# BLEmicro_IMU_ArduinoV3.net
KiCad netlist of a schematic drawn in EAGLE
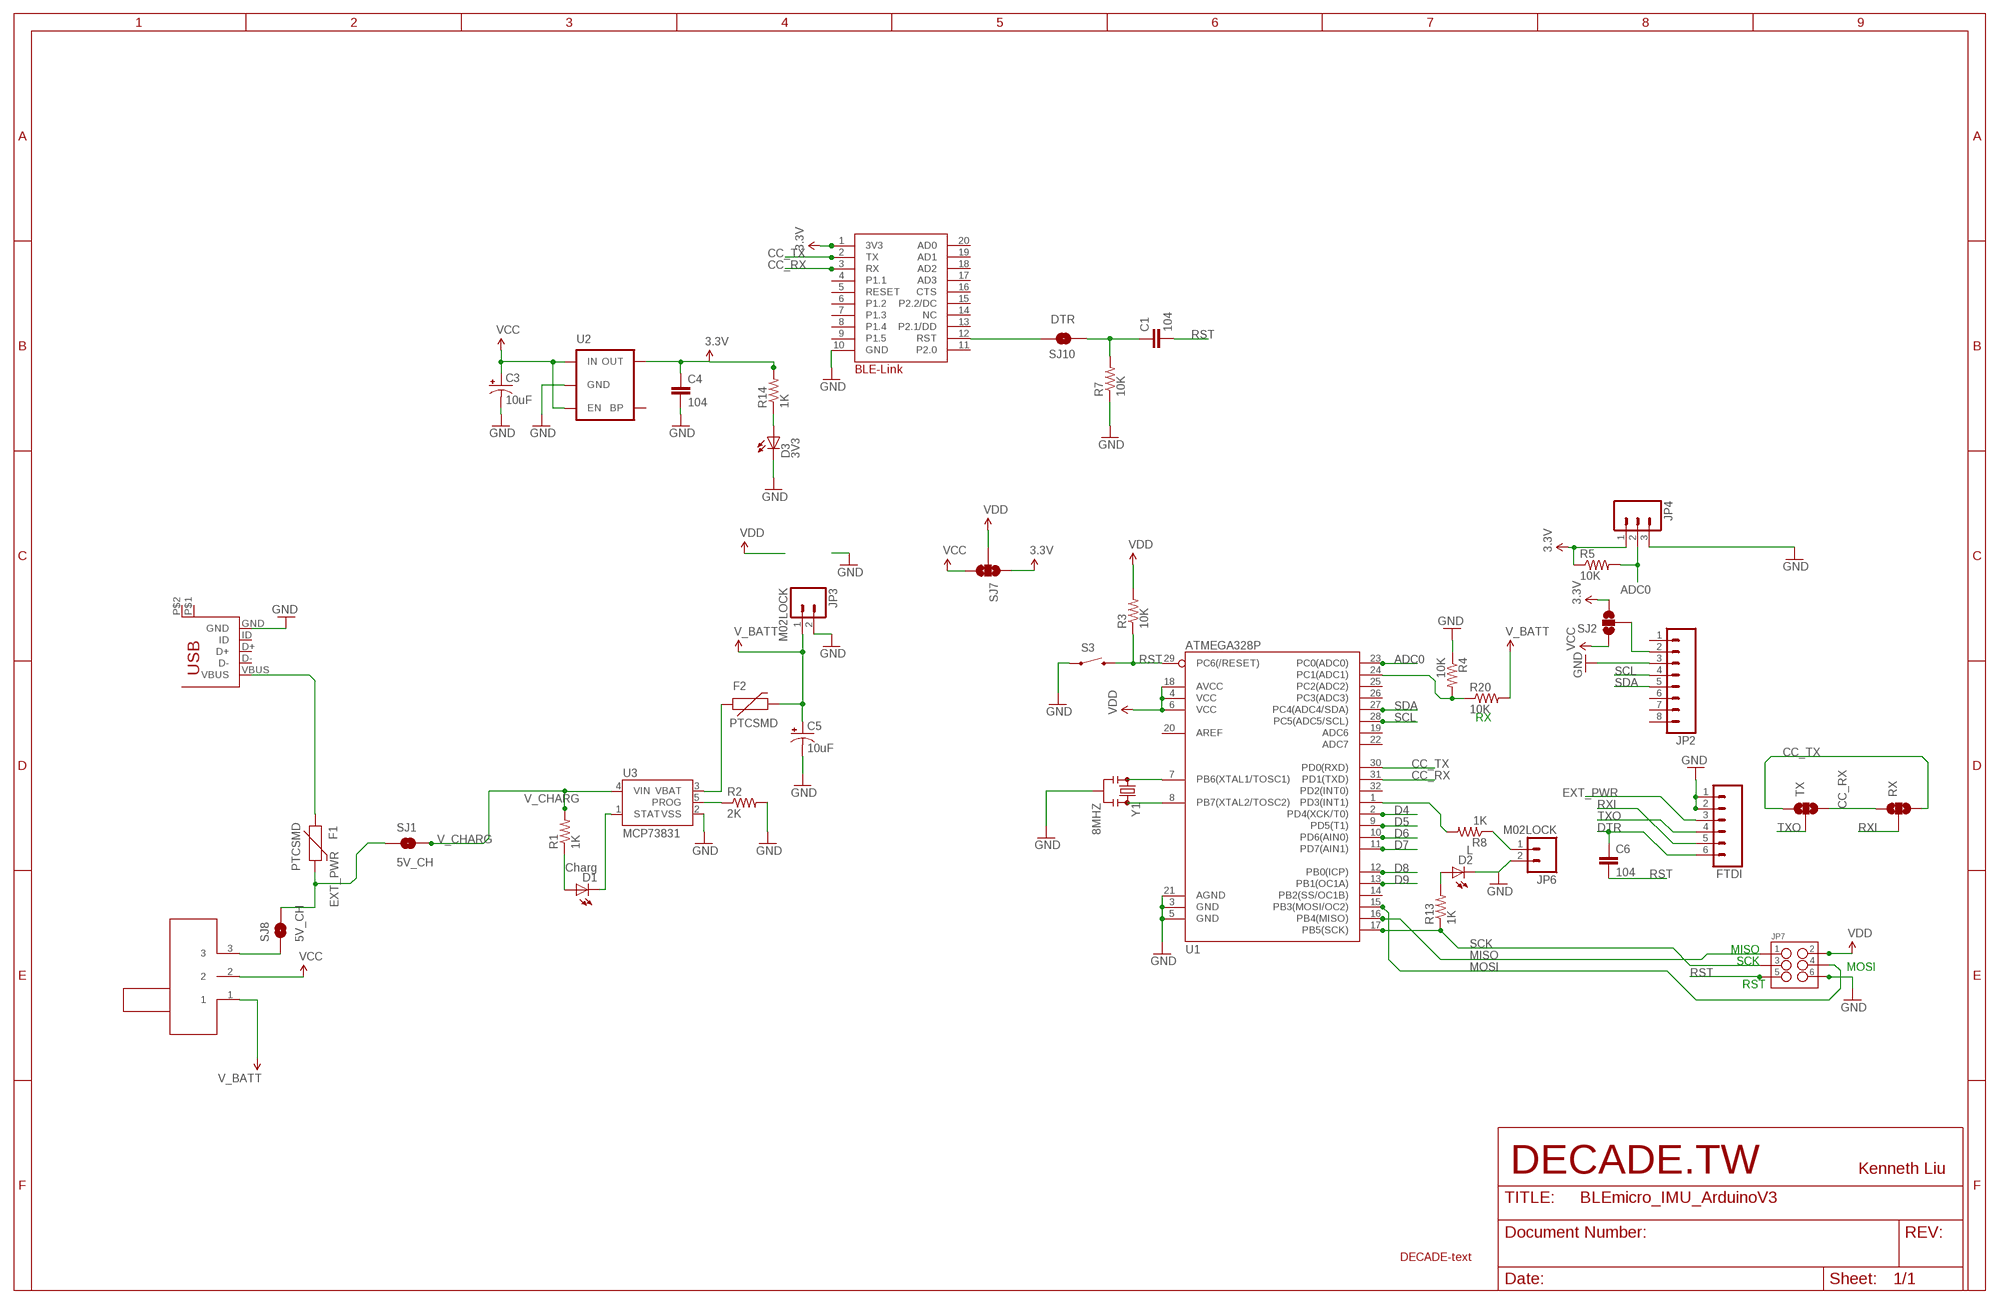
[diagram p0: schematic, sheet 1]

(export (version "E")
  (design (tool "Eeschema 10.0.6"))
  (components
    (comp (ref "C1")
      (value "104")
      (footprint "eagle-import:0603-CAP")
      (libsource (lib "eagle-import") (part "CAP0603-CAP"))
    )
    (comp (ref "C3")
      (value "10uF")
      (footprint "eagle-import:EIA3216")
      (libsource (lib "eagle-import") (part "CAP_POL1206"))
    )
    (comp (ref "C4")
      (value "104")
      (footprint "eagle-import:0603-CAP")
      (libsource (lib "eagle-import") (part "CAP0603-CAP"))
    )
    (comp (ref "C5")
      (value "10uF")
      (footprint "eagle-import:EIA3216")
      (libsource (lib "eagle-import") (part "CAP_POL1206"))
    )
    (comp (ref "C6")
      (value "104")
      (footprint "eagle-import:0603-CAP")
      (libsource (lib "eagle-import") (part "CAP0603-CAP"))
    )
    (comp (ref "D1")
      (value "Charg")
      (footprint "eagle-import:LED-0603")
      (libsource (lib "eagle-import") (part "LED-RED0603"))
    )
    (comp (ref "D2")
      (value "L")
      (footprint "eagle-import:LED-0603")
      (libsource (lib "eagle-import") (part "LED-RED0603"))
    )
    (comp (ref "D3")
      (value "3V3")
      (footprint "eagle-import:LED-0603")
      (libsource (lib "eagle-import") (part "LED-RED0603"))
    )
    (comp (ref "F1")
      (value "PTCSMD")
      (footprint "eagle-import:PTC-1206")
      (libsource (lib "eagle-import") (part "PTCSMD"))
    )
    (comp (ref "F2")
      (value "PTCSMD")
      (footprint "eagle-import:PTC-1206")
      (libsource (lib "eagle-import") (part "PTCSMD"))
    )
    (comp (ref "FTDI")
      (value "M06NO_SILK")
      (footprint "eagle-import:1X06_NO_SILK")
      (libsource (lib "eagle-import") (part "M06NO_SILK"))
    )
    (comp (ref "JP2")
      (value "M08NO_SILK")
      (footprint "eagle-import:1X08_NO_SILK")
      (libsource (lib "eagle-import") (part "M08NO_SILK"))
    )
    (comp (ref "JP3")
      (value "M02LOCK")
      (footprint "eagle-import:1X02_LOCK")
      (libsource (lib "eagle-import") (part "M02LOCK"))
    )
    (comp (ref "JP4")
      (value "M03PTH")
      (footprint "eagle-import:1X03")
      (libsource (lib "eagle-import") (part "M03PTH"))
    )
    (comp (ref "JP6")
      (value "M02LOCK")
      (footprint "eagle-import:1X02_LOCK")
      (libsource (lib "eagle-import") (part "M02LOCK"))
    )
    (comp (ref "JP7")
      (value "M03X2NO_SILK")
      (footprint "eagle-import:2X3-NS")
      (libsource (lib "eagle-import") (part "M03X2NO_SILK"))
    )
    (comp (ref "R1")
      (value "1K")
      (footprint "eagle-import:0603-RES")
      (libsource (lib "eagle-import") (part "RESISTOR0603-RES"))
    )
    (comp (ref "R2")
      (value "2K")
      (footprint "eagle-import:0603-RES")
      (libsource (lib "eagle-import") (part "RESISTOR0603-RES"))
    )
    (comp (ref "R3")
      (value "10K")
      (footprint "eagle-import:0603-RES")
      (libsource (lib "eagle-import") (part "RESISTOR0603-RES"))
    )
    (comp (ref "R4")
      (value "10K")
      (footprint "eagle-import:0603-RES")
      (libsource (lib "eagle-import") (part "RESISTOR0603-RES"))
    )
    (comp (ref "R5")
      (value "10K")
      (footprint "eagle-import:0603-RES")
      (libsource (lib "eagle-import") (part "RESISTOR0603-RES"))
    )
    (comp (ref "R7")
      (value "10K")
      (footprint "eagle-import:0603-RES")
      (libsource (lib "eagle-import") (part "RESISTOR0603-RES"))
    )
    (comp (ref "R8")
      (value "1K")
      (footprint "eagle-import:0603-RES")
      (libsource (lib "eagle-import") (part "RESISTOR0603-RES"))
    )
    (comp (ref "R13")
      (value "1K")
      (footprint "eagle-import:0603-RES")
      (libsource (lib "eagle-import") (part "RESISTOR0603-RES"))
    )
    (comp (ref "R14")
      (value "1K")
      (footprint "eagle-import:0603-RES")
      (libsource (lib "eagle-import") (part "RESISTOR0603-RES"))
    )
    (comp (ref "R20")
      (value "10K")
      (footprint "eagle-import:0603-RES")
      (libsource (lib "eagle-import") (part "RESISTOR0603-RES"))
    )
    (comp (ref "RX")
      (value "SOLDERJUMPER_2WAYS")
      (footprint "eagle-import:SJ_3")
      (libsource (lib "eagle-import") (part "SOLDERJUMPER_2WAYS"))
    )
    (comp (ref "S3")
      (value "SWITCH-MOMENTARY-2SMD-1101NE")
      (footprint "eagle-import:TACTILE-SWITCH-1101NE")
      (libsource (lib "eagle-import") (part "SWITCH-MOMENTARY-2SMD-1101NE"))
    )
    (comp (ref "SJ1")
      (value "5V_CH")
      (footprint "eagle-import:SJ_2S")
      (libsource (lib "eagle-import") (part "SOLDERJUMPER-OLDNC"))
    )
    (comp (ref "SJ2")
      (value "SOLDERJUMPER_2WAYS")
      (footprint "eagle-import:SJ_3")
      (libsource (lib "eagle-import") (part "SOLDERJUMPER_2WAYS"))
    )
    (comp (ref "SJ7")
      (value "SOLDERJUMPER_2WAYS")
      (footprint "eagle-import:SJ_3")
      (libsource (lib "eagle-import") (part "SOLDERJUMPER_2WAYS"))
    )
    (comp (ref "SJ8")
      (value "5V_CH")
      (footprint "eagle-import:SJ_2S")
      (libsource (lib "eagle-import") (part "SOLDERJUMPER-OLDNC"))
    )
    (comp (ref "SJ10")
      (value "DTR")
      (footprint "eagle-import:SJ_2S")
      (libsource (lib "eagle-import") (part "SOLDERJUMPER-OLDNC"))
    )
    (comp (ref "TX")
      (value "SOLDERJUMPER_2WAYS")
      (footprint "eagle-import:SJ_3")
      (libsource (lib "eagle-import") (part "SOLDERJUMPER_2WAYS"))
    )
    (comp (ref "U$1")
      (value "BLE-LINK")
      (footprint "eagle-import:XBEE-1_LOCK")
      (libsource (lib "eagle-import") (part "BLE-LINK"))
    )
    (comp (ref "U$2")
      (value "USB_MICRO_7PIN")
      (footprint "eagle-import:USB-MICROB-7PIN")
      (libsource (lib "eagle-import") (part "USB_MICRO_7PIN"))
    )
    (comp (ref "U$4")
      (value "DECADE-SW-SMALL")
      (footprint "eagle-import:DECADE-SW-SM")
      (libsource (lib "eagle-import") (part "DECADE-SW-SMALL"))
    )
    (comp (ref "U$7")
      (value "DECADE-LOGO-TEXT")
      (footprint "eagle-import:DECADE-LOGO-TEXT")
      (libsource (lib "eagle-import") (part "DECADE-LOGO-TEXT"))
    )
    (comp (ref "U1")
      (value "ATMEGA328P")
      (footprint "eagle-import:TQFP32-08")
      (libsource (lib "eagle-import") (part "ATMEGA328_SMT"))
    )
    (comp (ref "U2")
      (value "MIC52053.3V")
      (footprint "eagle-import:SOT23-5")
      (libsource (lib "eagle-import") (part "MIC52053.3V"))
    )
    (comp (ref "U3")
      (value "MCP73831")
      (footprint "eagle-import:SOT23-5")
      (libsource (lib "eagle-import") (part "MCP73831"))
    )
    (comp (ref "Y1")
      (value "8MHZ")
      (footprint "eagle-import:RESONATOR-SMD")
      (libsource (lib "eagle-import") (part "RESONATOR8MHZ"))
    )
  )
  (nets
    (net (code "1") (name "/ADC0") (class "Default")
      (node (ref "JP4") (pin "2") (pinfunction "2_2") (pintype "passive"))
      (node (ref "R5") (pin "2") (pinfunction "2_2") (pintype "passive"))
      (node (ref "U1") (pin "23") (pinfunction "PC0(ADC0)_23") (pintype "bidirectional"))
    )
    (net (code "2") (name "/CC_RX") (class "Default")
      (node (ref "RX") (pin "1") (pinfunction "1_1") (pintype "passive"))
      (node (ref "TX") (pin "3") (pinfunction "3_3") (pintype "passive"))
      (node (ref "U$1") (pin "3") (pinfunction "RX_3") (pintype "bidirectional"))
      (node (ref "U1") (pin "31") (pinfunction "PD1(TXD)_31") (pintype "bidirectional"))
    )
    (net (code "3") (name "/CC_TX") (class "Default")
      (node (ref "RX") (pin "3") (pinfunction "3_3") (pintype "passive"))
      (node (ref "TX") (pin "1") (pinfunction "1_1") (pintype "passive"))
      (node (ref "U$1") (pin "2") (pinfunction "TX_2") (pintype "bidirectional"))
      (node (ref "U1") (pin "30") (pinfunction "PD0(RXD)_30") (pintype "bidirectional"))
    )
    (net (code "4") (name "/D4") (class "Default")
      (node (ref "U1") (pin "2") (pinfunction "PD4(XCK/T0)_2") (pintype "bidirectional"))
    )
    (net (code "5") (name "/D5") (class "Default")
      (node (ref "U1") (pin "9") (pinfunction "PD5(T1)_9") (pintype "bidirectional"))
    )
    (net (code "6") (name "/D6") (class "Default")
      (node (ref "U1") (pin "10") (pinfunction "PD6(AIN0)_10") (pintype "bidirectional"))
    )
    (net (code "7") (name "/D7") (class "Default")
      (node (ref "U1") (pin "11") (pinfunction "PD7(AIN1)_11") (pintype "bidirectional"))
    )
    (net (code "8") (name "/D8") (class "Default")
      (node (ref "U1") (pin "12") (pinfunction "PB0(ICP)_12") (pintype "bidirectional"))
    )
    (net (code "9") (name "/D9") (class "Default")
      (node (ref "U1") (pin "13") (pinfunction "PB1(OC1A)_13") (pintype "bidirectional"))
    )
    (net (code "10") (name "/DTR") (class "Default")
      (node (ref "C6") (pin "1") (pinfunction "1_1") (pintype "passive"))
      (node (ref "FTDI") (pin "6") (pinfunction "6_6") (pintype "passive"))
    )
    (net (code "11") (name "/EXT_PWR") (class "Default")
      (node (ref "F1") (pin "2") (pinfunction "2_2") (pintype "bidirectional"))
      (node (ref "FTDI") (pin "3") (pinfunction "3_3") (pintype "passive"))
      (node (ref "SJ1") (pin "1") (pinfunction "1_1") (pintype "passive"))
      (node (ref "SJ8") (pin "2") (pinfunction "2_2") (pintype "passive"))
    )
    (net (code "12") (name "/MISO") (class "Default")
      (node (ref "JP7") (pin "1") (pinfunction "1_1") (pintype "bidirectional"))
      (node (ref "U1") (pin "16") (pinfunction "PB4(MISO)_16") (pintype "bidirectional"))
    )
    (net (code "13") (name "/MOSI") (class "Default")
      (node (ref "JP7") (pin "4") (pinfunction "4_4") (pintype "bidirectional"))
      (node (ref "U1") (pin "15") (pinfunction "PB3(MOSI/OC2)_15") (pintype "bidirectional"))
    )
    (net (code "14") (name "/RST") (class "Default")
      (node (ref "C1") (pin "2") (pinfunction "2_2") (pintype "passive"))
      (node (ref "C6") (pin "2") (pinfunction "2_2") (pintype "passive"))
      (node (ref "JP7") (pin "5") (pinfunction "5_5") (pintype "bidirectional"))
      (node (ref "R3") (pin "1") (pinfunction "1_1") (pintype "passive"))
      (node (ref "S3") (pin "2") (pinfunction "2_2") (pintype "passive"))
      (node (ref "U1") (pin "29") (pinfunction "PC6(/RESET)_29") (pintype "bidirectional"))
    )
    (net (code "15") (name "/RXI") (class "Default")
      (node (ref "FTDI") (pin "5") (pinfunction "5_5") (pintype "passive"))
      (node (ref "RX") (pin "2") (pinfunction "2_2") (pintype "passive"))
    )
    (net (code "16") (name "/SCK") (class "Default")
      (node (ref "JP7") (pin "3") (pinfunction "3_3") (pintype "bidirectional"))
      (node (ref "R13") (pin "1") (pinfunction "1_1") (pintype "passive"))
      (node (ref "U1") (pin "17") (pinfunction "PB5(SCK)_17") (pintype "bidirectional"))
    )
    (net (code "17") (name "/SCL") (class "Default")
      (node (ref "JP2") (pin "4") (pinfunction "4_4") (pintype "passive"))
      (node (ref "U1") (pin "28") (pinfunction "PC5(ADC5/SCL)_28") (pintype "bidirectional"))
    )
    (net (code "18") (name "/SDA") (class "Default")
      (node (ref "JP2") (pin "5") (pinfunction "5_5") (pintype "passive"))
      (node (ref "U1") (pin "27") (pinfunction "PC4(ADC4/SDA)_27") (pintype "bidirectional"))
    )
    (net (code "19") (name "/TXO") (class "Default")
      (node (ref "FTDI") (pin "4") (pinfunction "4_4") (pintype "passive"))
      (node (ref "TX") (pin "2") (pinfunction "2_2") (pintype "passive"))
    )
    (net (code "20") (name "/V_CHARG") (class "Default")
      (node (ref "R1") (pin "2") (pinfunction "2_2") (pintype "passive"))
      (node (ref "SJ1") (pin "2") (pinfunction "2_2") (pintype "passive"))
      (node (ref "U3") (pin "4") (pinfunction "VIN_4") (pintype "power_in"))
    )
    (net (code "21") (name "3.3V") (class "Default")
      (node (ref "C4") (pin "1") (pinfunction "1_1") (pintype "passive"))
      (node (ref "JP4") (pin "1") (pinfunction "1_1") (pintype "passive"))
      (node (ref "R14") (pin "2") (pinfunction "2_2") (pintype "passive"))
      (node (ref "R5") (pin "1") (pinfunction "1_1") (pintype "passive"))
      (node (ref "SJ2") (pin "3") (pinfunction "3_3") (pintype "passive"))
      (node (ref "SJ7") (pin "1") (pinfunction "1_1") (pintype "passive"))
      (node (ref "U$1") (pin "1") (pinfunction "3V3_1") (pintype "bidirectional"))
      (node (ref "U2") (pin "5") (pinfunction "OUT_5") (pintype "passive"))
    )
    (net (code "22") (name "GND") (class "Default")
      (node (ref "C3") (pin "C") (pinfunction "-_C") (pintype "passive"))
      (node (ref "C4") (pin "2") (pinfunction "2_2") (pintype "passive"))
      (node (ref "C5") (pin "C") (pinfunction "-_C") (pintype "passive"))
      (node (ref "D2") (pin "C") (pinfunction "C_C") (pintype "passive"))
      (node (ref "D3") (pin "C") (pinfunction "C_C") (pintype "passive"))
      (node (ref "FTDI") (pin "1") (pinfunction "1_1") (pintype "passive"))
      (node (ref "FTDI") (pin "2") (pinfunction "2_2") (pintype "passive"))
      (node (ref "JP2") (pin "3") (pinfunction "3_3") (pintype "passive"))
      (node (ref "JP3") (pin "2") (pinfunction "2_2") (pintype "passive"))
      (node (ref "JP4") (pin "3") (pinfunction "3_3") (pintype "passive"))
      (node (ref "JP6") (pin "2") (pinfunction "2_2") (pintype "passive"))
      (node (ref "JP7") (pin "6") (pinfunction "6_6") (pintype "bidirectional"))
      (node (ref "R2") (pin "2") (pinfunction "2_2") (pintype "passive"))
      (node (ref "R4") (pin "1") (pinfunction "1_1") (pintype "passive"))
      (node (ref "R7") (pin "1") (pinfunction "1_1") (pintype "passive"))
      (node (ref "S3") (pin "1") (pinfunction "1_1") (pintype "passive"))
      (node (ref "U$1") (pin "10") (pinfunction "GND_10") (pintype "bidirectional"))
      (node (ref "U$2") (pin "GND") (pinfunction "GND_GND") (pintype "bidirectional"))
      (node (ref "U1") (pin "21") (pinfunction "AGND_21") (pintype "bidirectional"))
      (node (ref "U1") (pin "3") (pinfunction "GND_3") (pintype "bidirectional"))
      (node (ref "U1") (pin "5") (pinfunction "GND_5") (pintype "bidirectional"))
      (node (ref "U2") (pin "2") (pinfunction "GND_2") (pintype "input"))
      (node (ref "U3") (pin "2") (pinfunction "VSS_2") (pintype "power_in"))
      (node (ref "Y1") (pin "2") (pinfunction "2_2") (pintype "passive"))
    )
    (net (code "23") (name "Net-(C1-Pad1)") (class "Default")
      (node (ref "C1") (pin "1") (pinfunction "1_1") (pintype "passive"))
      (node (ref "R7") (pin "2") (pinfunction "2_2") (pintype "passive"))
      (node (ref "SJ10") (pin "1") (pinfunction "1_1") (pintype "passive"))
    )
    (net (code "24") (name "Net-(D1-PadA)") (class "Default")
      (node (ref "D1") (pin "A") (pinfunction "A_A") (pintype "passive"))
      (node (ref "R1") (pin "1") (pinfunction "1_1") (pintype "passive"))
    )
    (net (code "25") (name "Net-(D2-PadA)") (class "Default")
      (node (ref "D2") (pin "A") (pinfunction "A_A") (pintype "passive"))
      (node (ref "R13") (pin "2") (pinfunction "2_2") (pintype "passive"))
    )
    (net (code "26") (name "Net-(D3-PadA)") (class "Default")
      (node (ref "D3") (pin "A") (pinfunction "A_A") (pintype "passive"))
      (node (ref "R14") (pin "1") (pinfunction "1_1") (pintype "passive"))
    )
    (net (code "27") (name "Net-(F1-Pad1)") (class "Default")
      (node (ref "F1") (pin "1") (pinfunction "1_1") (pintype "bidirectional"))
      (node (ref "U$2") (pin "VBUS") (pinfunction "VBUS_VBUS") (pintype "bidirectional"))
    )
    (net (code "28") (name "Net-(JP2-Pad2)") (class "Default")
      (node (ref "JP2") (pin "2") (pinfunction "2_2") (pintype "passive"))
      (node (ref "SJ2") (pin "2") (pinfunction "2_2") (pintype "passive"))
    )
    (net (code "29") (name "Net-(JP6-Pad1)") (class "Default")
      (node (ref "JP6") (pin "1") (pinfunction "1_1") (pintype "passive"))
      (node (ref "R8") (pin "1") (pinfunction "1_1") (pintype "passive"))
    )
    (net (code "30") (name "Net-(SJ8-Pad1)") (class "Default")
      (node (ref "SJ8") (pin "1") (pinfunction "1_1") (pintype "passive"))
      (node (ref "U$4") (pin "3") (pinfunction "3_3") (pintype "bidirectional"))
    )
    (net (code "31") (name "Net-(U$1-RST)") (class "Default")
      (node (ref "SJ10") (pin "2") (pinfunction "2_2") (pintype "passive"))
      (node (ref "U$1") (pin "12") (pinfunction "RST_12") (pintype "bidirectional"))
    )
    (net (code "32") (name "Net-(U1-PB6(XTAL1{slash}TOSC1))") (class "Default")
      (node (ref "U1") (pin "7") (pinfunction "PB6(XTAL1/TOSC1)_7") (pintype "bidirectional"))
      (node (ref "Y1") (pin "1") (pinfunction "1_1") (pintype "passive"))
    )
    (net (code "33") (name "Net-(U1-PB7(XTAL2{slash}TOSC2))") (class "Default")
      (node (ref "U1") (pin "8") (pinfunction "PB7(XTAL2/TOSC2)_8") (pintype "bidirectional"))
      (node (ref "Y1") (pin "3") (pinfunction "3_3") (pintype "passive"))
    )
    (net (code "34") (name "Net-(U1-PC1(ADC1))") (class "Default")
      (node (ref "R20") (pin "1") (pinfunction "1_1") (pintype "passive"))
      (node (ref "R4") (pin "2") (pinfunction "2_2") (pintype "passive"))
      (node (ref "U1") (pin "24") (pinfunction "PC1(ADC1)_24") (pintype "bidirectional"))
    )
    (net (code "35") (name "Net-(U1-PD3(INT1))") (class "Default")
      (node (ref "R8") (pin "2") (pinfunction "2_2") (pintype "passive"))
      (node (ref "U1") (pin "1") (pinfunction "PD3(INT1)_1") (pintype "bidirectional"))
    )
    (net (code "36") (name "Net-(U3-PROG)") (class "Default")
      (node (ref "R2") (pin "1") (pinfunction "1_1") (pintype "passive"))
      (node (ref "U3") (pin "5") (pinfunction "PROG_5") (pintype "input"))
    )
    (net (code "37") (name "Net-(U3-STAT)") (class "Default")
      (node (ref "D1") (pin "C") (pinfunction "C_C") (pintype "passive"))
      (node (ref "U3") (pin "1") (pinfunction "STAT_1") (pintype "output"))
    )
    (net (code "38") (name "Net-(U3-VBAT)") (class "Default")
      (node (ref "F2") (pin "1") (pinfunction "1_1") (pintype "bidirectional"))
      (node (ref "U3") (pin "3") (pinfunction "VBAT_3") (pintype "power_in"))
    )
    (net (code "39") (name "VCC") (class "Default")
      (node (ref "C3") (pin "A") (pinfunction "+_A") (pintype "passive"))
      (node (ref "SJ2") (pin "1") (pinfunction "1_1") (pintype "passive"))
      (node (ref "SJ7") (pin "3") (pinfunction "3_3") (pintype "passive"))
      (node (ref "U$4") (pin "2") (pinfunction "2_2") (pintype "bidirectional"))
      (node (ref "U2") (pin "1") (pinfunction "IN_1") (pintype "input"))
      (node (ref "U2") (pin "3") (pinfunction "EN_3") (pintype "input"))
    )
    (net (code "40") (name "VDD") (class "Default")
      (node (ref "JP7") (pin "2") (pinfunction "2_2") (pintype "bidirectional"))
      (node (ref "R3") (pin "2") (pinfunction "2_2") (pintype "passive"))
      (node (ref "SJ7") (pin "2") (pinfunction "2_2") (pintype "passive"))
      (node (ref "U1") (pin "18") (pinfunction "AVCC_18") (pintype "bidirectional"))
      (node (ref "U1") (pin "4") (pinfunction "VCC_4") (pintype "bidirectional"))
      (node (ref "U1") (pin "6") (pinfunction "VCC_6") (pintype "bidirectional"))
    )
    (net (code "41") (name "V_BATT") (class "Default")
      (node (ref "C5") (pin "A") (pinfunction "+_A") (pintype "passive"))
      (node (ref "F2") (pin "2") (pinfunction "2_2") (pintype "bidirectional"))
      (node (ref "JP3") (pin "1") (pinfunction "1_1") (pintype "passive"))
      (node (ref "R20") (pin "2") (pinfunction "2_2") (pintype "passive"))
      (node (ref "U$4") (pin "1") (pinfunction "1_1") (pintype "bidirectional"))
    )
    (net (code "42") (name "unconnected-(JP2-Pad1)") (class "Default")
      (node (ref "JP2") (pin "1") (pinfunction "1_1") (pintype "passive"))
    )
    (net (code "43") (name "unconnected-(JP2-Pad6)") (class "Default")
      (node (ref "JP2") (pin "6") (pinfunction "6_6") (pintype "passive"))
    )
    (net (code "44") (name "unconnected-(JP2-Pad7)") (class "Default")
      (node (ref "JP2") (pin "7") (pinfunction "7_7") (pintype "passive"))
    )
    (net (code "45") (name "unconnected-(JP2-Pad8)") (class "Default")
      (node (ref "JP2") (pin "8") (pinfunction "8_8") (pintype "passive"))
    )
    (net (code "46") (name "unconnected-(U$1-AD0-Pad20)") (class "Default")
      (node (ref "U$1") (pin "20") (pinfunction "AD0_20") (pintype "bidirectional"))
    )
    (net (code "47") (name "unconnected-(U$1-AD1-Pad19)") (class "Default")
      (node (ref "U$1") (pin "19") (pinfunction "AD1_19") (pintype "bidirectional"))
    )
    (net (code "48") (name "unconnected-(U$1-AD2-Pad18)") (class "Default")
      (node (ref "U$1") (pin "18") (pinfunction "AD2_18") (pintype "bidirectional"))
    )
    (net (code "49") (name "unconnected-(U$1-AD3-Pad17)") (class "Default")
      (node (ref "U$1") (pin "17") (pinfunction "AD3_17") (pintype "bidirectional"))
    )
    (net (code "50") (name "unconnected-(U$1-CTS-Pad16)") (class "Default")
      (node (ref "U$1") (pin "16") (pinfunction "CTS_16") (pintype "bidirectional"))
    )
    (net (code "51") (name "unconnected-(U$1-NC-Pad14)") (class "Default")
      (node (ref "U$1") (pin "14") (pinfunction "NC_14") (pintype "bidirectional"))
    )
    (net (code "52") (name "unconnected-(U$1-P1.1-Pad4)") (class "Default")
      (node (ref "U$1") (pin "4") (pinfunction "P1.1_4") (pintype "bidirectional"))
    )
    (net (code "53") (name "unconnected-(U$1-P1.2-Pad6)") (class "Default")
      (node (ref "U$1") (pin "6") (pinfunction "P1.2_6") (pintype "bidirectional"))
    )
    (net (code "54") (name "unconnected-(U$1-P1.3-Pad7)") (class "Default")
      (node (ref "U$1") (pin "7") (pinfunction "P1.3_7") (pintype "bidirectional"))
    )
    (net (code "55") (name "unconnected-(U$1-P1.4-Pad8)") (class "Default")
      (node (ref "U$1") (pin "8") (pinfunction "P1.4_8") (pintype "bidirectional"))
    )
    (net (code "56") (name "unconnected-(U$1-P1.5-Pad9)") (class "Default")
      (node (ref "U$1") (pin "9") (pinfunction "P1.5_9") (pintype "bidirectional"))
    )
    (net (code "57") (name "unconnected-(U$1-P2.0-Pad11)") (class "Default")
      (node (ref "U$1") (pin "11") (pinfunction "P2.0_11") (pintype "bidirectional"))
    )
    (net (code "58") (name "unconnected-(U$1-P2.1{slash}DD-Pad13)") (class "Default")
      (node (ref "U$1") (pin "13") (pinfunction "P2.1/DD_13") (pintype "bidirectional"))
    )
    (net (code "59") (name "unconnected-(U$1-P2.2{slash}DC-Pad15)") (class "Default")
      (node (ref "U$1") (pin "15") (pinfunction "P2.2/DC_15") (pintype "bidirectional"))
    )
    (net (code "60") (name "unconnected-(U$1-RESET-Pad5)") (class "Default")
      (node (ref "U$1") (pin "5") (pinfunction "RESET_5") (pintype "bidirectional"))
    )
    (net (code "61") (name "unconnected-(U$2-PadD+)") (class "Default")
      (node (ref "U$2") (pin "D+") (pinfunction "D+_D+") (pintype "bidirectional"))
    )
    (net (code "62") (name "unconnected-(U$2-PadD-)") (class "Default")
      (node (ref "U$2") (pin "D-") (pinfunction "D-_D-") (pintype "bidirectional"))
    )
    (net (code "63") (name "unconnected-(U$2-PadID)") (class "Default")
      (node (ref "U$2") (pin "ID") (pinfunction "ID_ID") (pintype "bidirectional"))
    )
    (net (code "64") (name "unconnected-(U$2-PadP$1)") (class "Default")
      (node (ref "U$2") (pin "P$1") (pinfunction "P$1_P$1") (pintype "bidirectional"))
    )
    (net (code "65") (name "unconnected-(U$2-PadP$2)") (class "Default")
      (node (ref "U$2") (pin "P$2") (pinfunction "P$2_P$2") (pintype "bidirectional"))
    )
    (net (code "66") (name "unconnected-(U1-ADC6-Pad19)") (class "Default")
      (node (ref "U1") (pin "19") (pinfunction "ADC6_19") (pintype "bidirectional"))
    )
    (net (code "67") (name "unconnected-(U1-ADC7-Pad22)") (class "Default")
      (node (ref "U1") (pin "22") (pinfunction "ADC7_22") (pintype "bidirectional"))
    )
    (net (code "68") (name "unconnected-(U1-AREF-Pad20)") (class "Default")
      (node (ref "U1") (pin "20") (pinfunction "AREF_20") (pintype "bidirectional"))
    )
    (net (code "69") (name "unconnected-(U1-PB2(SS{slash}OC1B)-Pad14)") (class "Default")
      (node (ref "U1") (pin "14") (pinfunction "PB2(SS/OC1B)_14") (pintype "bidirectional"))
    )
    (net (code "70") (name "unconnected-(U1-PC2(ADC2)-Pad25)") (class "Default")
      (node (ref "U1") (pin "25") (pinfunction "PC2(ADC2)_25") (pintype "bidirectional"))
    )
    (net (code "71") (name "unconnected-(U1-PC3(ADC3)-Pad26)") (class "Default")
      (node (ref "U1") (pin "26") (pinfunction "PC3(ADC3)_26") (pintype "bidirectional"))
    )
    (net (code "72") (name "unconnected-(U1-PD2(INT0)-Pad32)") (class "Default")
      (node (ref "U1") (pin "32") (pinfunction "PD2(INT0)_32") (pintype "bidirectional"))
    )
    (net (code "73") (name "unconnected-(U2-BP-Pad4)") (class "Default")
      (node (ref "U2") (pin "4") (pinfunction "BP_4") (pintype "input"))
    )
  )
)
